# main.net
KiCad netlist of a schematic drawn in Altium Designer
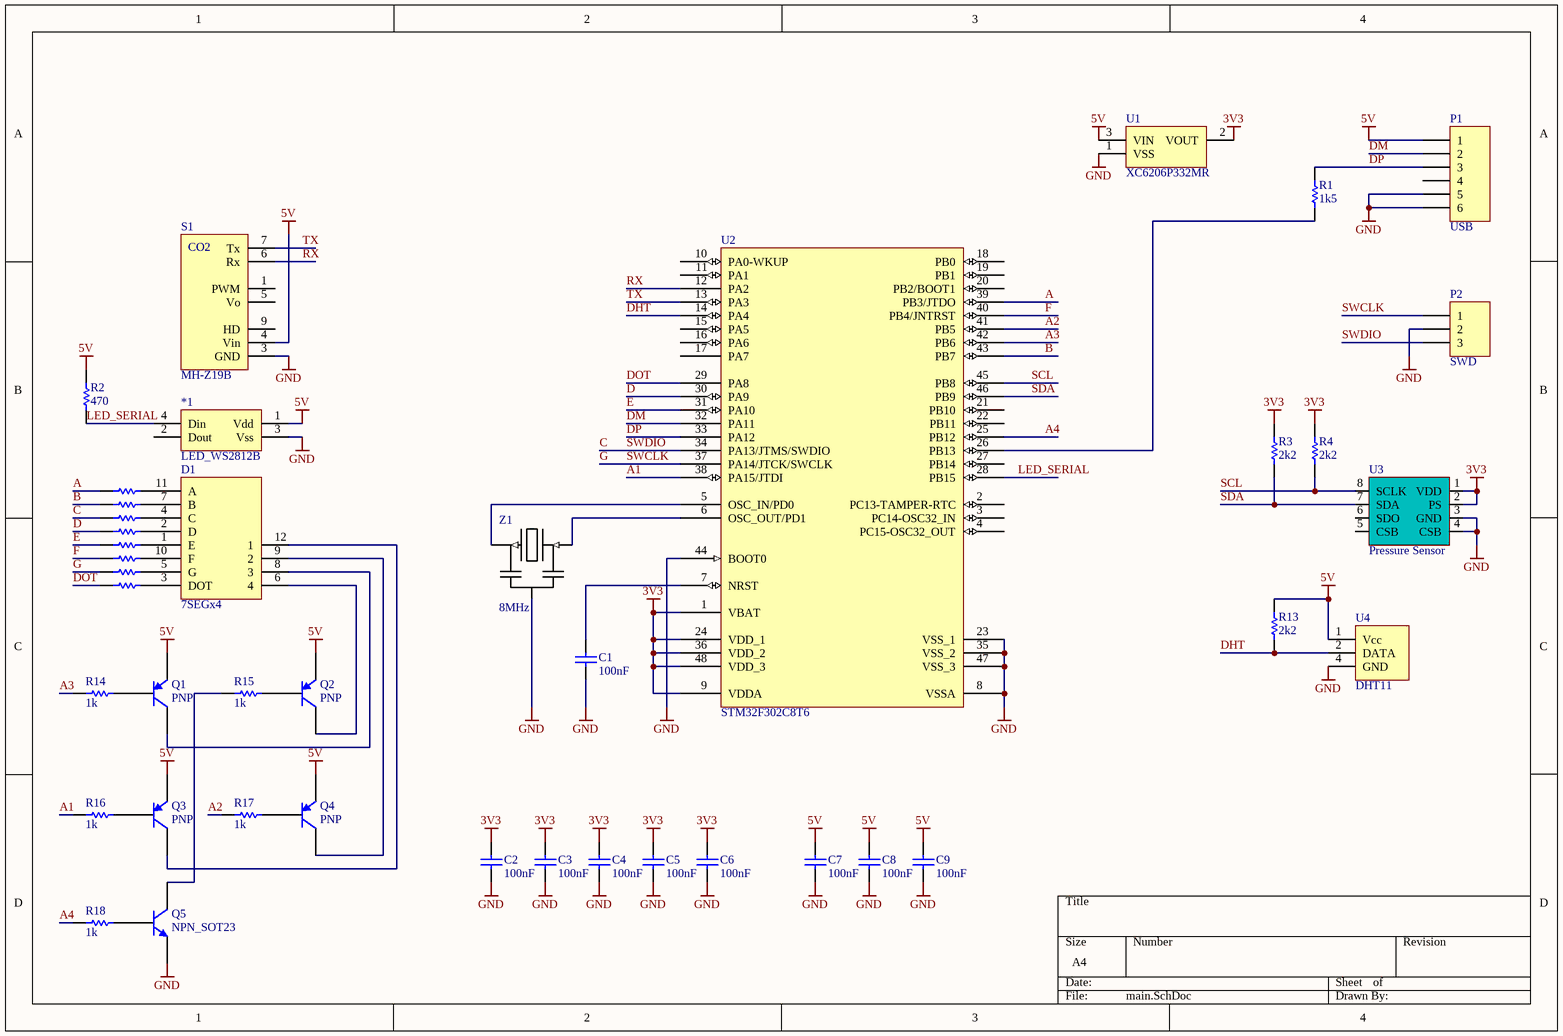
[diagram p0: main.SchDoc]

(export (version "E")
  (design (tool "Eeschema 10.0.6"))
  (components
    (comp (ref "*1")
      (value "LED_WS2812B")
      (footprint "LED_WS2812b")
      (libsource (lib "EDDLib") (part "LED_WS2812B"))
    )
    (comp (ref "C1")
      (value "100nF")
      (footprint "RC_0603")
      (description "Capacitor")
      (libsource (lib "Miscellaneous Devices") (part "Cap"))
    )
    (comp (ref "C2")
      (value "100nF")
      (footprint "RC_0603")
      (description "Capacitor")
      (libsource (lib "Miscellaneous Devices") (part "Cap"))
    )
    (comp (ref "C3")
      (value "100nF")
      (footprint "RC_0603")
      (description "Capacitor")
      (libsource (lib "Miscellaneous Devices") (part "Cap"))
    )
    (comp (ref "C4")
      (value "100nF")
      (footprint "RC_0603")
      (description "Capacitor")
      (libsource (lib "Miscellaneous Devices") (part "Cap"))
    )
    (comp (ref "C5")
      (value "100nF")
      (footprint "RC_0603")
      (description "Capacitor")
      (libsource (lib "Miscellaneous Devices") (part "Cap"))
    )
    (comp (ref "C6")
      (value "100nF")
      (footprint "RC_0603")
      (description "Capacitor")
      (libsource (lib "Miscellaneous Devices") (part "Cap"))
    )
    (comp (ref "C7")
      (value "100nF")
      (footprint "RC_0603")
      (description "Capacitor")
      (libsource (lib "Miscellaneous Devices") (part "Cap"))
    )
    (comp (ref "C8")
      (value "100nF")
      (footprint "RC_0603")
      (description "Capacitor")
      (libsource (lib "Miscellaneous Devices") (part "Cap"))
    )
    (comp (ref "C9")
      (value "100nF")
      (footprint "RC_0603")
      (description "Capacitor")
      (libsource (lib "Miscellaneous Devices") (part "Cap"))
    )
    (comp (ref "D1") (value "7SEGx4") (footprint "7SEG_4X_MEDIUM") (libsource (lib "EDDLib") (part "7SEGx4")))
    (comp (ref "P1")
      (value "USB")
      (footprint "RR_USB_MICRO_#1")
      (description "Header, 6-Pin")
      (fields (field (name "PUBLISHER") "Altium Limited"))
      (libsource (lib "Miscellaneous Connectors") (part "Header 6"))
    )
    (comp (ref "P2")
      (value "SWD")
      (footprint "MHDR1X3")
      (description "Header, 3-Pin")
      (fields (field (name "PUBLISHER") "Altium Limited"))
      (libsource (lib "Miscellaneous Connectors") (part "Header 3"))
    )
    (comp (ref "Q1")
      (value "PNP")
      (footprint "SOT-23B_L")
      (description "PNP Bipolar Transistor")
      (fields (field (name "PUBLISHER") "Altium Limited"))
      (libsource (lib "EDDLib") (part "PNP_SOT23"))
    )
    (comp (ref "Q2")
      (value "PNP")
      (footprint "SOT-23B_L")
      (description "PNP Bipolar Transistor")
      (fields (field (name "PUBLISHER") "Altium Limited"))
      (libsource (lib "EDDLib") (part "PNP_SOT23"))
    )
    (comp (ref "Q3")
      (value "PNP")
      (footprint "SOT-23B_L")
      (description "PNP Bipolar Transistor")
      (fields (field (name "PUBLISHER") "Altium Limited"))
      (libsource (lib "EDDLib") (part "PNP_SOT23"))
    )
    (comp (ref "Q4")
      (value "PNP")
      (footprint "SOT-23B_L")
      (description "PNP Bipolar Transistor")
      (fields (field (name "PUBLISHER") "Altium Limited"))
      (libsource (lib "EDDLib") (part "PNP_SOT23"))
    )
    (comp (ref "Q5")
      (value "NPN_SOT23")
      (footprint "SOT-23B_L")
      (description "NPN Bipolar Transistor")
      (fields (field (name "PUBLISHER") "Altium Limited"))
      (libsource (lib "EDDLib") (part "NPN_SOT23"))
    )
    (comp (ref "R1")
      (value "1k5")
      (footprint "RR_0603")
      (description "Resistor")
      (libsource (lib "Miscellaneous Devices") (part "Res1"))
    )
    (comp (ref "R2")
      (value "470")
      (footprint "RR_0603")
      (description "Resistor")
      (libsource (lib "Miscellaneous Devices") (part "Res1"))
    )
    (comp (ref "R3")
      (value "2k2")
      (footprint "RR_0603")
      (description "Resistor")
      (libsource (lib "Miscellaneous Devices") (part "Res1"))
    )
    (comp (ref "R4")
      (value "2k2")
      (footprint "RR_0603")
      (description "Resistor")
      (libsource (lib "Miscellaneous Devices") (part "Res1"))
    )
    (comp (ref "R5")
      (value "220")
      (footprint "RR_0603")
      (description "Resistor")
      (libsource (lib "Miscellaneous Devices") (part "Res1"))
    )
    (comp (ref "R6")
      (value "220")
      (footprint "RR_0603")
      (description "Resistor")
      (libsource (lib "Miscellaneous Devices") (part "Res1"))
    )
    (comp (ref "R7")
      (value "220")
      (footprint "RR_0603")
      (description "Resistor")
      (libsource (lib "Miscellaneous Devices") (part "Res1"))
    )
    (comp (ref "R8")
      (value "220")
      (footprint "RR_0603")
      (description "Resistor")
      (libsource (lib "Miscellaneous Devices") (part "Res1"))
    )
    (comp (ref "R9")
      (value "220")
      (footprint "RR_0603")
      (description "Resistor")
      (libsource (lib "Miscellaneous Devices") (part "Res1"))
    )
    (comp (ref "R10")
      (value "220")
      (footprint "RR_0603")
      (description "Resistor")
      (libsource (lib "Miscellaneous Devices") (part "Res1"))
    )
    (comp (ref "R11")
      (value "220")
      (footprint "RR_0603")
      (description "Resistor")
      (libsource (lib "Miscellaneous Devices") (part "Res1"))
    )
    (comp (ref "R12")
      (value "220")
      (footprint "RR_0603")
      (description "Resistor")
      (libsource (lib "Miscellaneous Devices") (part "Res1"))
    )
    (comp (ref "R13")
      (value "2k2")
      (footprint "RR_0603")
      (description "Resistor")
      (libsource (lib "Miscellaneous Devices") (part "Res1"))
    )
    (comp (ref "R14")
      (value "1k")
      (footprint "RR_0603")
      (description "Resistor")
      (libsource (lib "Miscellaneous Devices") (part "Res1"))
    )
    (comp (ref "R15")
      (value "1k")
      (footprint "RR_0603")
      (description "Resistor")
      (libsource (lib "Miscellaneous Devices") (part "Res1"))
    )
    (comp (ref "R16")
      (value "1k")
      (footprint "RR_0603")
      (description "Resistor")
      (libsource (lib "Miscellaneous Devices") (part "Res1"))
    )
    (comp (ref "R17")
      (value "1k")
      (footprint "RR_0603")
      (description "Resistor")
      (libsource (lib "Miscellaneous Devices") (part "Res1"))
    )
    (comp (ref "R18")
      (value "1k")
      (footprint "RR_0603")
      (description "Resistor")
      (libsource (lib "Miscellaneous Devices") (part "Res1"))
    )
    (comp (ref "S1") (value "MH-Z19B") (footprint "MH_Z19B") (libsource (lib "EDDLib") (part "MH_Z19B")))
    (comp (ref "U1")
      (value "XC6206P332MR")
      (footprint "RR_SOT-23")
      (libsource (lib "Schlib1") (part "Component_4_1"))
    )
    (comp (ref "U2")
      (value "STM32F302C8T6")
      (footprint "LQFP48_N")
      (fields (field (name "PUBLISHER") "Altium Limited"))
      (libsource (lib "EDDLib") (part "STM32F302C8T6"))
    )
    (comp (ref "U3")
      (value "Pressure Sensor")
      (footprint "MS5611-01BA03")
      (description "Pressure Sensor - MS5611-01BA03")
      (libsource (lib "OpenPilot") (part "MS5611-01BA03"))
    )
    (comp (ref "U4") (value "DHT11") (footprint "DHT11") (libsource (lib "EDDLib") (part "DHT11")))
    (comp (ref "Z1")
      (value "8MHz")
      (footprint "RR_CRYSTAL_3.2X1.3")
      (description "XTAL 8.0000MHZ 33PF SMD")
      (fields (field (name "MANUFACTURER") "Murata Electronics"))
      (libsource (lib "EDDLib") (part "CSTCE8M00G55-R0"))
    )
  )
  (nets
    (net (code "1") (name "/A") (class "Default")
      (node (ref "R5") (pin "1") (pinfunction "1_1") (pintype "passive"))
      (node (ref "U2") (pin "39") (pinfunction "PB3/JTDO_39") (pintype "bidirectional"))
    )
    (net (code "2") (name "/A1") (class "Default")
      (node (ref "R16") (pin "1") (pinfunction "1_1") (pintype "passive"))
      (node (ref "U2") (pin "38") (pinfunction "PA15/JTDI_38") (pintype "bidirectional"))
    )
    (net (code "3") (name "/A2") (class "Default")
      (node (ref "R17") (pin "1") (pinfunction "1_1") (pintype "passive"))
      (node (ref "U2") (pin "41") (pinfunction "PB5_41") (pintype "bidirectional"))
    )
    (net (code "4") (name "/A3") (class "Default")
      (node (ref "R14") (pin "1") (pinfunction "1_1") (pintype "passive"))
      (node (ref "U2") (pin "42") (pinfunction "PB6_42") (pintype "bidirectional"))
    )
    (net (code "5") (name "/A4") (class "Default")
      (node (ref "R18") (pin "1") (pinfunction "1_1") (pintype "passive"))
      (node (ref "U2") (pin "25") (pinfunction "PB12_25") (pintype "bidirectional"))
    )
    (net (code "6") (name "/B") (class "Default")
      (node (ref "R6") (pin "1") (pinfunction "1_1") (pintype "passive"))
      (node (ref "U2") (pin "43") (pinfunction "PB7_43") (pintype "bidirectional"))
    )
    (net (code "7") (name "/C") (class "Default")
      (node (ref "P2") (pin "3") (pinfunction "3_3") (pintype "passive"))
      (node (ref "R7") (pin "1") (pinfunction "1_1") (pintype "passive"))
      (node (ref "U2") (pin "34") (pinfunction "PA13/JTMS/SWDIO_34") (pintype "passive"))
    )
    (net (code "8") (name "/D") (class "Default")
      (node (ref "R8") (pin "1") (pinfunction "1_1") (pintype "passive"))
      (node (ref "U2") (pin "30") (pinfunction "PA9_30") (pintype "bidirectional"))
    )
    (net (code "9") (name "/DHT") (class "Default")
      (node (ref "R13") (pin "1") (pinfunction "1_1") (pintype "passive"))
      (node (ref "U2") (pin "14") (pinfunction "PA4_14") (pintype "bidirectional"))
      (node (ref "U4") (pin "2") (pinfunction "DATA_2") (pintype "passive"))
    )
    (net (code "10") (name "/DM") (class "Default")
      (node (ref "P1") (pin "2") (pinfunction "2_2") (pintype "passive"))
      (node (ref "U2") (pin "32") (pinfunction "PA11_32") (pintype "passive"))
    )
    (net (code "11") (name "/DOT") (class "Default")
      (node (ref "R12") (pin "1") (pinfunction "1_1") (pintype "passive"))
      (node (ref "U2") (pin "29") (pinfunction "PA8_29") (pintype "passive"))
    )
    (net (code "12") (name "/DP") (class "Default")
      (node (ref "P1") (pin "3") (pinfunction "3_3") (pintype "passive"))
      (node (ref "R1") (pin "2") (pinfunction "2_2") (pintype "passive"))
      (node (ref "U2") (pin "33") (pinfunction "PA12_33") (pintype "passive"))
    )
    (net (code "13") (name "/E") (class "Default")
      (node (ref "R9") (pin "1") (pinfunction "1_1") (pintype "passive"))
      (node (ref "U2") (pin "31") (pinfunction "PA10_31") (pintype "bidirectional"))
    )
    (net (code "14") (name "/F") (class "Default")
      (node (ref "R10") (pin "1") (pinfunction "1_1") (pintype "passive"))
      (node (ref "U2") (pin "40") (pinfunction "PB4/JNTRST_40") (pintype "bidirectional"))
    )
    (net (code "15") (name "/G") (class "Default")
      (node (ref "P2") (pin "1") (pinfunction "1_1") (pintype "passive"))
      (node (ref "R11") (pin "1") (pinfunction "1_1") (pintype "passive"))
      (node (ref "U2") (pin "37") (pinfunction "PA14/JTCK/SWCLK_37") (pintype "passive"))
    )
    (net (code "16") (name "/LED_SERIAL") (class "Default")
      (node (ref "*1") (pin "4") (pinfunction "Din_4") (pintype "passive"))
      (node (ref "R2") (pin "1") (pinfunction "1_1") (pintype "passive"))
      (node (ref "U2") (pin "28") (pinfunction "PB15_28") (pintype "bidirectional"))
    )
    (net (code "17") (name "/RX") (class "Default")
      (node (ref "S1") (pin "6") (pinfunction "Rx_6") (pintype "passive"))
      (node (ref "U2") (pin "12") (pinfunction "PA2_12") (pintype "passive"))
    )
    (net (code "18") (name "/SCL") (class "Default")
      (node (ref "R4") (pin "1") (pinfunction "1_1") (pintype "passive"))
      (node (ref "U2") (pin "45") (pinfunction "PB8_45") (pintype "bidirectional"))
      (node (ref "U3") (pin "8") (pinfunction "SCLK_8") (pintype "passive"))
    )
    (net (code "19") (name "/SDA") (class "Default")
      (node (ref "R3") (pin "1") (pinfunction "1_1") (pintype "passive"))
      (node (ref "U2") (pin "46") (pinfunction "PB9_46") (pintype "bidirectional"))
      (node (ref "U3") (pin "7") (pinfunction "SDA_7") (pintype "passive"))
    )
    (net (code "20") (name "/TX") (class "Default")
      (node (ref "S1") (pin "7") (pinfunction "Tx_7") (pintype "passive"))
      (node (ref "U2") (pin "13") (pinfunction "PA3_13") (pintype "bidirectional"))
    )
    (net (code "21") (name "3V3") (class "Default")
      (node (ref "C2") (pin "2") (pinfunction "2_2") (pintype "passive"))
      (node (ref "C3") (pin "2") (pinfunction "2_2") (pintype "passive"))
      (node (ref "C4") (pin "2") (pinfunction "2_2") (pintype "passive"))
      (node (ref "C5") (pin "2") (pinfunction "2_2") (pintype "passive"))
      (node (ref "C6") (pin "2") (pinfunction "2_2") (pintype "passive"))
      (node (ref "R3") (pin "2") (pinfunction "2_2") (pintype "passive"))
      (node (ref "R4") (pin "2") (pinfunction "2_2") (pintype "passive"))
      (node (ref "U1") (pin "2") (pinfunction "VOUT_2") (pintype "passive"))
      (node (ref "U2") (pin "1") (pinfunction "VBAT_1") (pintype "power_in"))
      (node (ref "U2") (pin "24") (pinfunction "VDD_1_24") (pintype "power_in"))
      (node (ref "U2") (pin "36") (pinfunction "VDD_2_36") (pintype "power_in"))
      (node (ref "U2") (pin "48") (pinfunction "VDD_3_48") (pintype "power_in"))
      (node (ref "U2") (pin "9") (pinfunction "VDDA_9") (pintype "power_in"))
      (node (ref "U3") (pin "1") (pinfunction "VDD_1") (pintype "power_in"))
      (node (ref "U3") (pin "2") (pinfunction "PS_2") (pintype "passive"))
    )
    (net (code "22") (name "5V") (class "Default")
      (node (ref "*1") (pin "1") (pinfunction "Vdd_1") (pintype "passive"))
      (node (ref "C7") (pin "2") (pinfunction "2_2") (pintype "passive"))
      (node (ref "C8") (pin "2") (pinfunction "2_2") (pintype "passive"))
      (node (ref "C9") (pin "2") (pinfunction "2_2") (pintype "passive"))
      (node (ref "P1") (pin "1") (pinfunction "1_1") (pintype "passive"))
      (node (ref "Q1") (pin "2") (pinfunction "E_2") (pintype "passive"))
      (node (ref "Q2") (pin "2") (pinfunction "E_2") (pintype "passive"))
      (node (ref "Q3") (pin "2") (pinfunction "E_2") (pintype "passive"))
      (node (ref "Q4") (pin "2") (pinfunction "E_2") (pintype "passive"))
      (node (ref "R13") (pin "2") (pinfunction "2_2") (pintype "passive"))
      (node (ref "R2") (pin "2") (pinfunction "2_2") (pintype "passive"))
      (node (ref "S1") (pin "4") (pinfunction "Vin_4") (pintype "passive"))
      (node (ref "U1") (pin "3") (pinfunction "VIN_3") (pintype "passive"))
      (node (ref "U4") (pin "1") (pinfunction "Vcc_1") (pintype "passive"))
    )
    (net (code "23") (name "GND") (class "Default")
      (node (ref "*1") (pin "3") (pinfunction "Vss_3") (pintype "passive"))
      (node (ref "C1") (pin "1") (pinfunction "1_1") (pintype "passive"))
      (node (ref "C2") (pin "1") (pinfunction "1_1") (pintype "passive"))
      (node (ref "C3") (pin "1") (pinfunction "1_1") (pintype "passive"))
      (node (ref "C4") (pin "1") (pinfunction "1_1") (pintype "passive"))
      (node (ref "C5") (pin "1") (pinfunction "1_1") (pintype "passive"))
      (node (ref "C6") (pin "1") (pinfunction "1_1") (pintype "passive"))
      (node (ref "C7") (pin "1") (pinfunction "1_1") (pintype "passive"))
      (node (ref "C8") (pin "1") (pinfunction "1_1") (pintype "passive"))
      (node (ref "C9") (pin "1") (pinfunction "1_1") (pintype "passive"))
      (node (ref "P1") (pin "5") (pinfunction "5_5") (pintype "passive"))
      (node (ref "P1") (pin "6") (pinfunction "6_6") (pintype "passive"))
      (node (ref "P2") (pin "2") (pinfunction "2_2") (pintype "passive"))
      (node (ref "Q5") (pin "2") (pinfunction "E_2") (pintype "passive"))
      (node (ref "S1") (pin "3") (pinfunction "GND_3") (pintype "passive"))
      (node (ref "U1") (pin "1") (pinfunction "VSS_1") (pintype "passive"))
      (node (ref "U2") (pin "23") (pinfunction "VSS_1_23") (pintype "power_in"))
      (node (ref "U2") (pin "35") (pinfunction "VSS_2_35") (pintype "power_in"))
      (node (ref "U2") (pin "44") (pinfunction "BOOT0_44") (pintype "input"))
      (node (ref "U2") (pin "47") (pinfunction "VSS_3_47") (pintype "power_in"))
      (node (ref "U2") (pin "8") (pinfunction "VSSA_8") (pintype "power_in"))
      (node (ref "U3") (pin "3") (pinfunction "GND_3") (pintype "power_in"))
      (node (ref "U3") (pin "4") (pinfunction "CSB_4") (pintype "passive"))
      (node (ref "U4") (pin "4") (pinfunction "GND_4") (pintype "passive"))
      (node (ref "Z1") (pin "2") (pinfunction "GND_2") (pintype "passive"))
    )
    (net (code "24") (name "Net-(D1-1)") (class "Default")
      (node (ref "D1") (pin "12") (pinfunction "1_12") (pintype "passive"))
      (node (ref "Q3") (pin "3") (pinfunction "C_3") (pintype "passive"))
    )
    (net (code "25") (name "Net-(D1-2)") (class "Default")
      (node (ref "D1") (pin "9") (pinfunction "2_9") (pintype "passive"))
      (node (ref "Q4") (pin "3") (pinfunction "C_3") (pintype "passive"))
    )
    (net (code "26") (name "Net-(D1-3)") (class "Default")
      (node (ref "D1") (pin "8") (pinfunction "3_8") (pintype "passive"))
      (node (ref "Q1") (pin "3") (pinfunction "C_3") (pintype "passive"))
    )
    (net (code "27") (name "Net-(D1-4)") (class "Default")
      (node (ref "D1") (pin "6") (pinfunction "4_6") (pintype "passive"))
      (node (ref "Q2") (pin "3") (pinfunction "C_3") (pintype "passive"))
    )
    (net (code "28") (name "Net-(D1-A)") (class "Default")
      (node (ref "D1") (pin "11") (pinfunction "A_11") (pintype "passive"))
      (node (ref "R5") (pin "2") (pinfunction "2_2") (pintype "passive"))
    )
    (net (code "29") (name "Net-(D1-B)") (class "Default")
      (node (ref "D1") (pin "7") (pinfunction "B_7") (pintype "passive"))
      (node (ref "R6") (pin "2") (pinfunction "2_2") (pintype "passive"))
    )
    (net (code "30") (name "Net-(D1-C)") (class "Default")
      (node (ref "D1") (pin "4") (pinfunction "C_4") (pintype "passive"))
      (node (ref "R7") (pin "2") (pinfunction "2_2") (pintype "passive"))
    )
    (net (code "31") (name "Net-(D1-D)") (class "Default")
      (node (ref "D1") (pin "2") (pinfunction "D_2") (pintype "passive"))
      (node (ref "R8") (pin "2") (pinfunction "2_2") (pintype "passive"))
    )
    (net (code "32") (name "Net-(D1-DOT)") (class "Default")
      (node (ref "D1") (pin "3") (pinfunction "DOT_3") (pintype "passive"))
      (node (ref "R12") (pin "2") (pinfunction "2_2") (pintype "passive"))
    )
    (net (code "33") (name "Net-(D1-E)") (class "Default")
      (node (ref "D1") (pin "1") (pinfunction "E_1") (pintype "passive"))
      (node (ref "R9") (pin "2") (pinfunction "2_2") (pintype "passive"))
    )
    (net (code "34") (name "Net-(D1-F)") (class "Default")
      (node (ref "D1") (pin "10") (pinfunction "F_10") (pintype "passive"))
      (node (ref "R10") (pin "2") (pinfunction "2_2") (pintype "passive"))
    )
    (net (code "35") (name "Net-(D1-G)") (class "Default")
      (node (ref "D1") (pin "5") (pinfunction "G_5") (pintype "passive"))
      (node (ref "R11") (pin "2") (pinfunction "2_2") (pintype "passive"))
    )
    (net (code "36") (name "Net-(Q1-B)") (class "Default")
      (node (ref "Q1") (pin "1") (pinfunction "B_1") (pintype "passive"))
      (node (ref "R14") (pin "2") (pinfunction "2_2") (pintype "passive"))
    )
    (net (code "37") (name "Net-(Q2-B)") (class "Default")
      (node (ref "Q2") (pin "1") (pinfunction "B_1") (pintype "passive"))
      (node (ref "R15") (pin "2") (pinfunction "2_2") (pintype "passive"))
    )
    (net (code "38") (name "Net-(Q3-B)") (class "Default")
      (node (ref "Q3") (pin "1") (pinfunction "B_1") (pintype "passive"))
      (node (ref "R16") (pin "2") (pinfunction "2_2") (pintype "passive"))
    )
    (net (code "39") (name "Net-(Q4-B)") (class "Default")
      (node (ref "Q4") (pin "1") (pinfunction "B_1") (pintype "passive"))
      (node (ref "R17") (pin "2") (pinfunction "2_2") (pintype "passive"))
    )
    (net (code "40") (name "Net-(Q5-B)") (class "Default")
      (node (ref "Q5") (pin "1") (pinfunction "B_1") (pintype "passive"))
      (node (ref "R18") (pin "2") (pinfunction "2_2") (pintype "passive"))
    )
    (net (code "41") (name "Net-(Q5-C)") (class "Default")
      (node (ref "Q5") (pin "3") (pinfunction "C_3") (pintype "passive"))
      (node (ref "R15") (pin "1") (pinfunction "1_1") (pintype "passive"))
    )
    (net (code "42") (name "Net-(U2-NRST)") (class "Default")
      (node (ref "C1") (pin "2") (pinfunction "2_2") (pintype "passive"))
      (node (ref "U2") (pin "7") (pinfunction "NRST_7") (pintype "bidirectional"))
    )
    (net (code "43") (name "Net-(U2-OSC_IN{slash}PD0)") (class "Default")
      (node (ref "U2") (pin "5") (pinfunction "OSC_IN/PD0_5") (pintype "passive"))
      (node (ref "Z1") (pin "1") (pinfunction "X1_1") (pintype "output"))
    )
    (net (code "44") (name "Net-(U2-OSC_OUT{slash}PD1)") (class "Default")
      (node (ref "U2") (pin "6") (pinfunction "OSC_OUT/PD1_6") (pintype "passive"))
      (node (ref "Z1") (pin "3") (pinfunction "X2_3") (pintype "input"))
    )
    (net (code "45") (name "Net-(U2-PB13)") (class "Default")
      (node (ref "R1") (pin "1") (pinfunction "1_1") (pintype "passive"))
      (node (ref "U2") (pin "26") (pinfunction "PB13_26") (pintype "bidirectional"))
    )
    (net (code "46") (name "unconnected-(*1-Dout-Pad2)") (class "Default")
      (node (ref "*1") (pin "2") (pinfunction "Dout_2") (pintype "passive"))
    )
    (net (code "47") (name "unconnected-(P1-Pad4)") (class "Default")
      (node (ref "P1") (pin "4") (pinfunction "4_4") (pintype "passive"))
    )
    (net (code "48") (name "unconnected-(S1-HD-Pad9)") (class "Default")
      (node (ref "S1") (pin "9") (pinfunction "HD_9") (pintype "passive"))
    )
    (net (code "49") (name "unconnected-(S1-PWM-Pad1)") (class "Default")
      (node (ref "S1") (pin "1") (pinfunction "PWM_1") (pintype "passive"))
    )
    (net (code "50") (name "unconnected-(S1-Vo-Pad5)") (class "Default")
      (node (ref "S1") (pin "5") (pinfunction "Vo_5") (pintype "passive"))
    )
    (net (code "51") (name "unconnected-(U2-PA0-WKUP-Pad10)") (class "Default")
      (node (ref "U2") (pin "10") (pinfunction "PA0-WKUP_10") (pintype "bidirectional"))
    )
    (net (code "52") (name "unconnected-(U2-PA1-Pad11)") (class "Default")
      (node (ref "U2") (pin "11") (pinfunction "PA1_11") (pintype "bidirectional"))
    )
    (net (code "53") (name "unconnected-(U2-PA5-Pad15)") (class "Default")
      (node (ref "U2") (pin "15") (pinfunction "PA5_15") (pintype "bidirectional"))
    )
    (net (code "54") (name "unconnected-(U2-PA6-Pad16)") (class "Default")
      (node (ref "U2") (pin "16") (pinfunction "PA6_16") (pintype "bidirectional"))
    )
    (net (code "55") (name "unconnected-(U2-PA7-Pad17)") (class "Default")
      (node (ref "U2") (pin "17") (pinfunction "PA7_17") (pintype "passive"))
    )
    (net (code "56") (name "unconnected-(U2-PB0-Pad18)") (class "Default")
      (node (ref "U2") (pin "18") (pinfunction "PB0_18") (pintype "bidirectional"))
    )
    (net (code "57") (name "unconnected-(U2-PB1-Pad19)") (class "Default")
      (node (ref "U2") (pin "19") (pinfunction "PB1_19") (pintype "bidirectional"))
    )
    (net (code "58") (name "unconnected-(U2-PB2{slash}BOOT1-Pad20)") (class "Default")
      (node (ref "U2") (pin "20") (pinfunction "PB2/BOOT1_20") (pintype "bidirectional"))
    )
    (net (code "59") (name "unconnected-(U2-PB10-Pad21)") (class "Default")
      (node (ref "U2") (pin "21") (pinfunction "PB10_21") (pintype "bidirectional"))
    )
    (net (code "60") (name "unconnected-(U2-PB11-Pad22)") (class "Default")
      (node (ref "U2") (pin "22") (pinfunction "PB11_22") (pintype "bidirectional"))
    )
    (net (code "61") (name "unconnected-(U2-PB14-Pad27)") (class "Default")
      (node (ref "U2") (pin "27") (pinfunction "PB14_27") (pintype "bidirectional"))
    )
    (net (code "62") (name "unconnected-(U2-PC13-TAMPER-RTC-Pad2)") (class "Default")
      (node (ref "U2") (pin "2") (pinfunction "PC13-TAMPER-RTC_2") (pintype "bidirectional"))
    )
    (net (code "63") (name "unconnected-(U2-PC14-OSC32_IN-Pad3)") (class "Default")
      (node (ref "U2") (pin "3") (pinfunction "PC14-OSC32_IN_3") (pintype "bidirectional"))
    )
    (net (code "64") (name "unconnected-(U2-PC15-OSC32_OUT-Pad4)") (class "Default")
      (node (ref "U2") (pin "4") (pinfunction "PC15-OSC32_OUT_4") (pintype "bidirectional"))
    )
    (net (code "65") (name "unconnected-(U3-CSB-Pad5)") (class "Default")
      (node (ref "U3") (pin "5") (pinfunction "CSB_5") (pintype "passive"))
    )
    (net (code "66") (name "unconnected-(U3-SDO-Pad6)") (class "Default")
      (node (ref "U3") (pin "6") (pinfunction "SDO_6") (pintype "passive"))
    )
  )
)
